# untitled.net
KiCad netlist of a schematic drawn in EAGLE
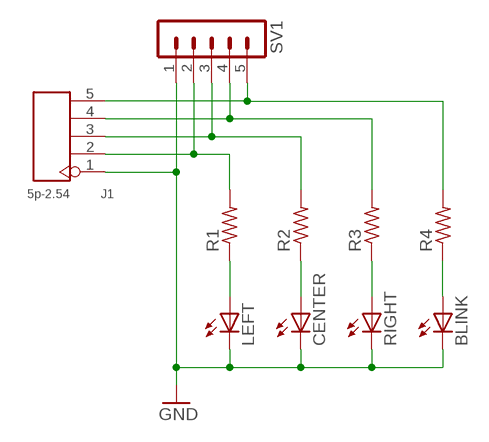
[diagram p0: schematic, sheet 1]

(export (version "E")
  (design (tool "Eeschema 10.0.6"))
  (components
    (comp (ref "BLINK")
      (value "LED5MM")
      (footprint "eagle-import:LED5MM")
      (libsource (lib "eagle-import") (part "LED5MM"))
    )
    (comp (ref "CENTER")
      (value "LED5MM")
      (footprint "eagle-import:LED5MM")
      (libsource (lib "eagle-import") (part "LED5MM"))
    )
    (comp (ref "J1")
      (value "5p-2.54")
      (footprint "eagle-import:H5-2.54-11.06X6.3MM")
      (fields (field (name "MPN") "GS019-5P-1"))
      (libsource (lib "eagle-import") (part "DIP-SCREW-TERMINAL(5P-2.54)"))
    )
    (comp (ref "LEFT")
      (value "LED5MM")
      (footprint "eagle-import:LED5MM")
      (libsource (lib "eagle-import") (part "LED5MM"))
    )
    (comp (ref "R1")
      (value "FLIPFLOP-RES")
      (footprint "eagle-import:0805-THM")
      (libsource (lib "eagle-import") (part "FLIPFLOP-RES"))
    )
    (comp (ref "R2")
      (value "FLIPFLOP-RES")
      (footprint "eagle-import:0805-THM")
      (libsource (lib "eagle-import") (part "FLIPFLOP-RES"))
    )
    (comp (ref "R3")
      (value "FLIPFLOP-RES")
      (footprint "eagle-import:0805-THM")
      (libsource (lib "eagle-import") (part "FLIPFLOP-RES"))
    )
    (comp (ref "R4")
      (value "FLIPFLOP-RES")
      (footprint "eagle-import:0805-THM")
      (libsource (lib "eagle-import") (part "FLIPFLOP-RES"))
    )
    (comp (ref "RIGHT")
      (value "LED5MM")
      (footprint "eagle-import:LED5MM")
      (libsource (lib "eagle-import") (part "LED5MM"))
    )
    (comp (ref "SV1")
      (value "MA05-1")
      (footprint "eagle-import:MA05-1")
      (libsource (lib "eagle-import") (part "MA05-1"))
    )
  )
  (nets
    (net (code "1") (name "GND") (class "Default")
      (node (ref "BLINK") (pin "K") (pinfunction "C_K") (pintype "passive"))
      (node (ref "CENTER") (pin "K") (pinfunction "C_K") (pintype "passive"))
      (node (ref "J1") (pin "1") (pinfunction "1_1") (pintype "bidirectional"))
      (node (ref "LEFT") (pin "K") (pinfunction "C_K") (pintype "passive"))
      (node (ref "RIGHT") (pin "K") (pinfunction "C_K") (pintype "passive"))
      (node (ref "SV1") (pin "1") (pinfunction "1_1") (pintype "passive"))
    )
    (net (code "2") (name "Net-(BLINK-PadA)") (class "Default")
      (node (ref "BLINK") (pin "A") (pinfunction "A_A") (pintype "passive"))
      (node (ref "R4") (pin "1") (pinfunction "1_1") (pintype "passive"))
    )
    (net (code "3") (name "Net-(CENTER-PadA)") (class "Default")
      (node (ref "CENTER") (pin "A") (pinfunction "A_A") (pintype "passive"))
      (node (ref "R2") (pin "1") (pinfunction "1_1") (pintype "passive"))
    )
    (net (code "4") (name "Net-(J1-Pad2)") (class "Default")
      (node (ref "J1") (pin "2") (pinfunction "2_2") (pintype "bidirectional"))
      (node (ref "R1") (pin "2") (pinfunction "2_2") (pintype "passive"))
      (node (ref "SV1") (pin "2") (pinfunction "2_2") (pintype "passive"))
    )
    (net (code "5") (name "Net-(J1-Pad3)") (class "Default")
      (node (ref "J1") (pin "3") (pinfunction "3_3") (pintype "bidirectional"))
      (node (ref "R2") (pin "2") (pinfunction "2_2") (pintype "passive"))
      (node (ref "SV1") (pin "3") (pinfunction "3_3") (pintype "passive"))
    )
    (net (code "6") (name "Net-(J1-Pad4)") (class "Default")
      (node (ref "J1") (pin "4") (pinfunction "4_4") (pintype "bidirectional"))
      (node (ref "R3") (pin "2") (pinfunction "2_2") (pintype "passive"))
      (node (ref "SV1") (pin "4") (pinfunction "4_4") (pintype "passive"))
    )
    (net (code "7") (name "Net-(J1-Pad5)") (class "Default")
      (node (ref "J1") (pin "5") (pinfunction "5_5") (pintype "bidirectional"))
      (node (ref "R4") (pin "2") (pinfunction "2_2") (pintype "passive"))
      (node (ref "SV1") (pin "5") (pinfunction "5_5") (pintype "passive"))
    )
    (net (code "8") (name "Net-(LEFT-PadA)") (class "Default")
      (node (ref "LEFT") (pin "A") (pinfunction "A_A") (pintype "passive"))
      (node (ref "R1") (pin "1") (pinfunction "1_1") (pintype "passive"))
    )
    (net (code "9") (name "Net-(R3-Pad1)") (class "Default")
      (node (ref "R3") (pin "1") (pinfunction "1_1") (pintype "passive"))
      (node (ref "RIGHT") (pin "A") (pinfunction "A_A") (pintype "passive"))
    )
  )
)
